# FPGA_DAC.net
KiCad netlist of a schematic drawn in Altium Designer
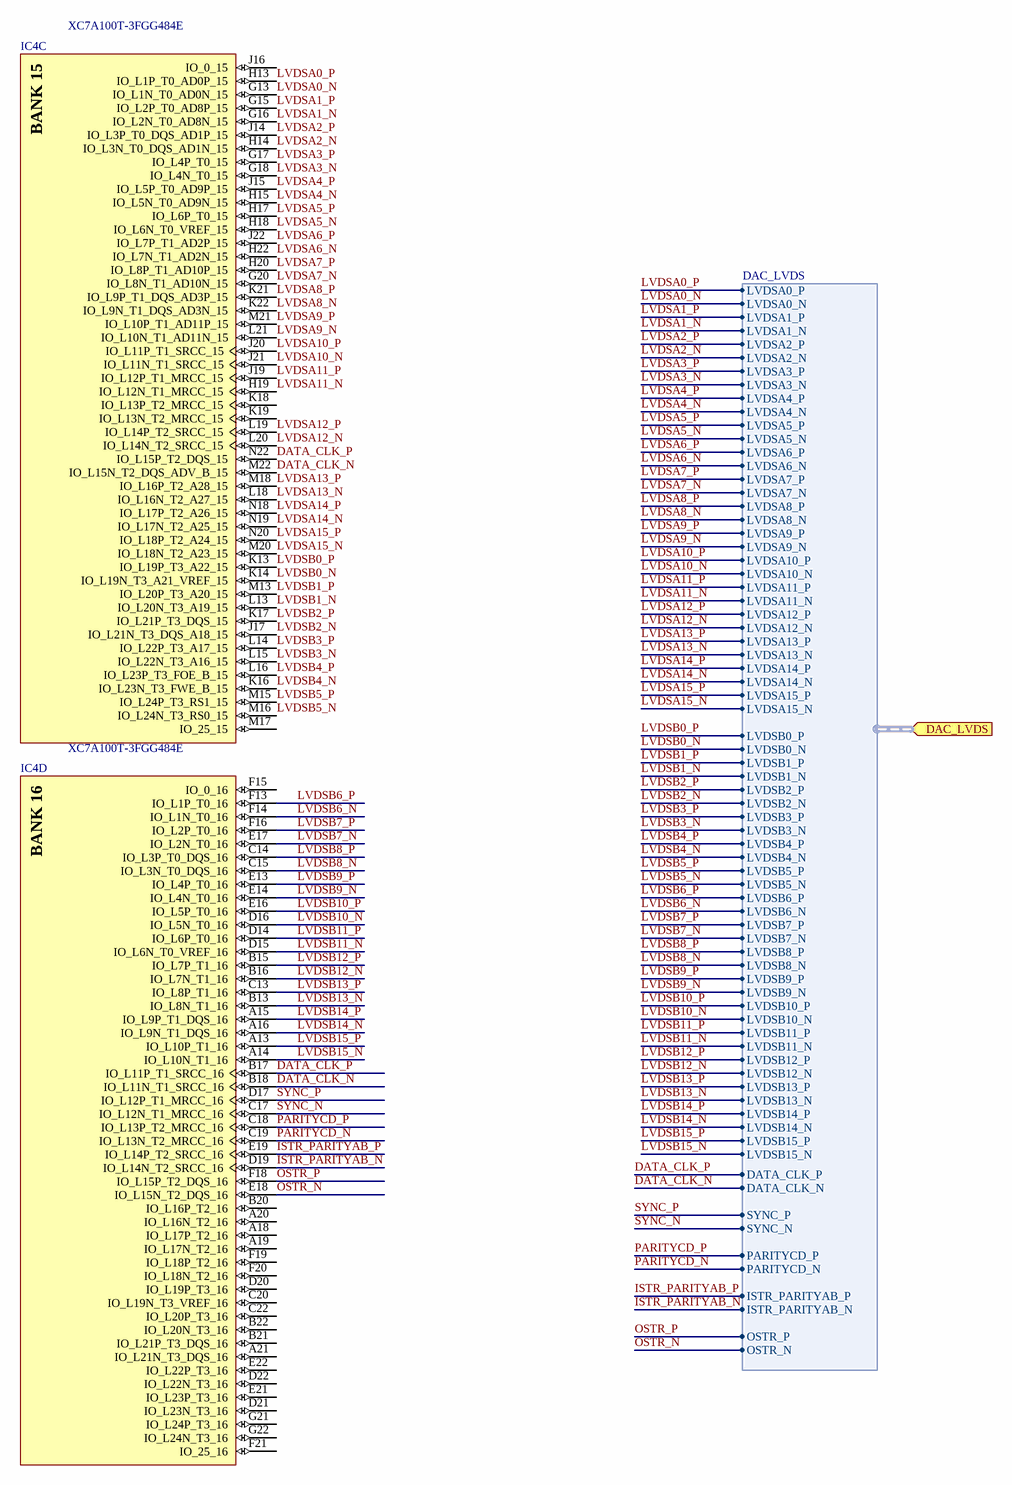
[diagram p0: FPGA_DAC.SchDoc]

(export (version "E")
  (design (tool "Eeschema 10.0.6"))
  (components
    (comp (ref "IC4")
      (value "XC7A100T-3FGG484E")
      (footprint "FGG484")
      (description "Artix-7 FPGA, 285 User I/Os, 4 GTP, 484-Ball BGA, Speed Grade 3, Extended Grade, Pb-Free")
      (fields (field (name "GENERIC PART NUMBER") "XC7A100T") (field (name "MANUFACTURER") "Xilinx"))
      (libsource (lib "Altium Content Vault") (part "XC7A100T-3FGG484E"))
    )
  )
  (nets
    (net (code "2") (name "/DATA_CLK_N") (class "Default")
      (node (ref "IC4") (pin "B18") (pinfunction "IO_L11N_T1_SRCC_16_B18") (pintype "bidirectional"))
      (node (ref "IC4") (pin "M22") (pinfunction "IO_L15N_T2_DQS_ADV_B_15_M22") (pintype "bidirectional"))
    )
    (net (code "3") (name "/DATA_CLK_P") (class "Default")
      (node (ref "IC4") (pin "B17") (pinfunction "IO_L11P_T1_SRCC_16_B17") (pintype "bidirectional"))
      (node (ref "IC4") (pin "N22") (pinfunction "IO_L15P_T2_DQS_15_N22") (pintype "bidirectional"))
    )
    (net (code "4") (name "/ISTR_PARITYAB_N") (class "Default")
      (node (ref "IC4") (pin "D19") (pinfunction "IO_L14N_T2_SRCC_16_D19") (pintype "bidirectional"))
    )
    (net (code "5") (name "/ISTR_PARITYAB_P") (class "Default")
      (node (ref "IC4") (pin "E19") (pinfunction "IO_L14P_T2_SRCC_16_E19") (pintype "bidirectional"))
    )
    (net (code "6") (name "/LVDSA0_N") (class "Default")
      (node (ref "IC4") (pin "G13") (pinfunction "IO_L1N_T0_AD0N_15_G13") (pintype "bidirectional"))
    )
    (net (code "7") (name "/LVDSA0_P") (class "Default")
      (node (ref "IC4") (pin "H13") (pinfunction "IO_L1P_T0_AD0P_15_H13") (pintype "bidirectional"))
    )
    (net (code "8") (name "/LVDSA1_N") (class "Default")
      (node (ref "IC4") (pin "G16") (pinfunction "IO_L2N_T0_AD8N_15_G16") (pintype "bidirectional"))
    )
    (net (code "9") (name "/LVDSA1_P") (class "Default")
      (node (ref "IC4") (pin "G15") (pinfunction "IO_L2P_T0_AD8P_15_G15") (pintype "bidirectional"))
    )
    (net (code "10") (name "/LVDSA2_N") (class "Default")
      (node (ref "IC4") (pin "H14") (pinfunction "IO_L3N_T0_DQS_AD1N_15_H14") (pintype "bidirectional"))
    )
    (net (code "11") (name "/LVDSA2_P") (class "Default")
      (node (ref "IC4") (pin "J14") (pinfunction "IO_L3P_T0_DQS_AD1P_15_J14") (pintype "bidirectional"))
    )
    (net (code "12") (name "/LVDSA3_N") (class "Default")
      (node (ref "IC4") (pin "G18") (pinfunction "IO_L4N_T0_15_G18") (pintype "bidirectional"))
    )
    (net (code "13") (name "/LVDSA3_P") (class "Default")
      (node (ref "IC4") (pin "G17") (pinfunction "IO_L4P_T0_15_G17") (pintype "bidirectional"))
    )
    (net (code "14") (name "/LVDSA4_N") (class "Default")
      (node (ref "IC4") (pin "H15") (pinfunction "IO_L5N_T0_AD9N_15_H15") (pintype "bidirectional"))
    )
    (net (code "15") (name "/LVDSA4_P") (class "Default")
      (node (ref "IC4") (pin "J15") (pinfunction "IO_L5P_T0_AD9P_15_J15") (pintype "bidirectional"))
    )
    (net (code "16") (name "/LVDSA5_N") (class "Default")
      (node (ref "IC4") (pin "H18") (pinfunction "IO_L6N_T0_VREF_15_H18") (pintype "bidirectional"))
    )
    (net (code "17") (name "/LVDSA5_P") (class "Default")
      (node (ref "IC4") (pin "H17") (pinfunction "IO_L6P_T0_15_H17") (pintype "bidirectional"))
    )
    (net (code "18") (name "/LVDSA6_N") (class "Default")
      (node (ref "IC4") (pin "H22") (pinfunction "IO_L7N_T1_AD2N_15_H22") (pintype "bidirectional"))
    )
    (net (code "19") (name "/LVDSA6_P") (class "Default")
      (node (ref "IC4") (pin "J22") (pinfunction "IO_L7P_T1_AD2P_15_J22") (pintype "bidirectional"))
    )
    (net (code "20") (name "/LVDSA7_N") (class "Default")
      (node (ref "IC4") (pin "G20") (pinfunction "IO_L8N_T1_AD10N_15_G20") (pintype "bidirectional"))
    )
    (net (code "21") (name "/LVDSA7_P") (class "Default")
      (node (ref "IC4") (pin "H20") (pinfunction "IO_L8P_T1_AD10P_15_H20") (pintype "bidirectional"))
    )
    (net (code "22") (name "/LVDSA8_N") (class "Default")
      (node (ref "IC4") (pin "K22") (pinfunction "IO_L9N_T1_DQS_AD3N_15_K22") (pintype "bidirectional"))
    )
    (net (code "23") (name "/LVDSA8_P") (class "Default")
      (node (ref "IC4") (pin "K21") (pinfunction "IO_L9P_T1_DQS_AD3P_15_K21") (pintype "bidirectional"))
    )
    (net (code "24") (name "/LVDSA9_N") (class "Default")
      (node (ref "IC4") (pin "L21") (pinfunction "IO_L10N_T1_AD11N_15_L21") (pintype "bidirectional"))
    )
    (net (code "25") (name "/LVDSA9_P") (class "Default")
      (node (ref "IC4") (pin "M21") (pinfunction "IO_L10P_T1_AD11P_15_M21") (pintype "bidirectional"))
    )
    (net (code "26") (name "/LVDSA10_N") (class "Default")
      (node (ref "IC4") (pin "J21") (pinfunction "IO_L11N_T1_SRCC_15_J21") (pintype "bidirectional"))
    )
    (net (code "27") (name "/LVDSA10_P") (class "Default")
      (node (ref "IC4") (pin "J20") (pinfunction "IO_L11P_T1_SRCC_15_J20") (pintype "bidirectional"))
    )
    (net (code "28") (name "/LVDSA11_N") (class "Default")
      (node (ref "IC4") (pin "H19") (pinfunction "IO_L12N_T1_MRCC_15_H19") (pintype "bidirectional"))
    )
    (net (code "29") (name "/LVDSA11_P") (class "Default")
      (node (ref "IC4") (pin "J19") (pinfunction "IO_L12P_T1_MRCC_15_J19") (pintype "bidirectional"))
    )
    (net (code "30") (name "/LVDSA12_N") (class "Default")
      (node (ref "IC4") (pin "L20") (pinfunction "IO_L14N_T2_SRCC_15_L20") (pintype "bidirectional"))
    )
    (net (code "31") (name "/LVDSA12_P") (class "Default")
      (node (ref "IC4") (pin "L19") (pinfunction "IO_L14P_T2_SRCC_15_L19") (pintype "bidirectional"))
    )
    (net (code "32") (name "/LVDSA13_N") (class "Default")
      (node (ref "IC4") (pin "L18") (pinfunction "IO_L16N_T2_A27_15_L18") (pintype "bidirectional"))
    )
    (net (code "33") (name "/LVDSA13_P") (class "Default")
      (node (ref "IC4") (pin "M18") (pinfunction "IO_L16P_T2_A28_15_M18") (pintype "bidirectional"))
    )
    (net (code "34") (name "/LVDSA14_N") (class "Default")
      (node (ref "IC4") (pin "N19") (pinfunction "IO_L17N_T2_A25_15_N19") (pintype "bidirectional"))
    )
    (net (code "35") (name "/LVDSA14_P") (class "Default")
      (node (ref "IC4") (pin "N18") (pinfunction "IO_L17P_T2_A26_15_N18") (pintype "bidirectional"))
    )
    (net (code "36") (name "/LVDSA15_N") (class "Default")
      (node (ref "IC4") (pin "M20") (pinfunction "IO_L18N_T2_A23_15_M20") (pintype "bidirectional"))
    )
    (net (code "37") (name "/LVDSA15_P") (class "Default")
      (node (ref "IC4") (pin "N20") (pinfunction "IO_L18P_T2_A24_15_N20") (pintype "bidirectional"))
    )
    (net (code "38") (name "/LVDSB0_N") (class "Default")
      (node (ref "IC4") (pin "K14") (pinfunction "IO_L19N_T3_A21_VREF_15_K14") (pintype "bidirectional"))
    )
    (net (code "39") (name "/LVDSB0_P") (class "Default")
      (node (ref "IC4") (pin "K13") (pinfunction "IO_L19P_T3_A22_15_K13") (pintype "bidirectional"))
    )
    (net (code "40") (name "/LVDSB1_N") (class "Default")
      (node (ref "IC4") (pin "L13") (pinfunction "IO_L20N_T3_A19_15_L13") (pintype "bidirectional"))
    )
    (net (code "41") (name "/LVDSB1_P") (class "Default")
      (node (ref "IC4") (pin "M13") (pinfunction "IO_L20P_T3_A20_15_M13") (pintype "bidirectional"))
    )
    (net (code "42") (name "/LVDSB2_N") (class "Default")
      (node (ref "IC4") (pin "J17") (pinfunction "IO_L21N_T3_DQS_A18_15_J17") (pintype "bidirectional"))
    )
    (net (code "43") (name "/LVDSB2_P") (class "Default")
      (node (ref "IC4") (pin "K17") (pinfunction "IO_L21P_T3_DQS_15_K17") (pintype "bidirectional"))
    )
    (net (code "44") (name "/LVDSB3_N") (class "Default")
      (node (ref "IC4") (pin "L15") (pinfunction "IO_L22N_T3_A16_15_L15") (pintype "bidirectional"))
    )
    (net (code "45") (name "/LVDSB3_P") (class "Default")
      (node (ref "IC4") (pin "L14") (pinfunction "IO_L22P_T3_A17_15_L14") (pintype "bidirectional"))
    )
    (net (code "46") (name "/LVDSB4_N") (class "Default")
      (node (ref "IC4") (pin "K16") (pinfunction "IO_L23N_T3_FWE_B_15_K16") (pintype "bidirectional"))
    )
    (net (code "47") (name "/LVDSB4_P") (class "Default")
      (node (ref "IC4") (pin "L16") (pinfunction "IO_L23P_T3_FOE_B_15_L16") (pintype "bidirectional"))
    )
    (net (code "48") (name "/LVDSB5_N") (class "Default")
      (node (ref "IC4") (pin "M16") (pinfunction "IO_L24N_T3_RS0_15_M16") (pintype "bidirectional"))
    )
    (net (code "49") (name "/LVDSB5_P") (class "Default")
      (node (ref "IC4") (pin "M15") (pinfunction "IO_L24P_T3_RS1_15_M15") (pintype "bidirectional"))
    )
    (net (code "50") (name "/LVDSB6_N") (class "Default")
      (node (ref "IC4") (pin "F14") (pinfunction "IO_L1N_T0_16_F14") (pintype "bidirectional"))
    )
    (net (code "51") (name "/LVDSB6_P") (class "Default")
      (node (ref "IC4") (pin "F13") (pinfunction "IO_L1P_T0_16_F13") (pintype "bidirectional"))
    )
    (net (code "52") (name "/LVDSB7_N") (class "Default")
      (node (ref "IC4") (pin "E17") (pinfunction "IO_L2N_T0_16_E17") (pintype "bidirectional"))
    )
    (net (code "53") (name "/LVDSB7_P") (class "Default")
      (node (ref "IC4") (pin "F16") (pinfunction "IO_L2P_T0_16_F16") (pintype "bidirectional"))
    )
    (net (code "54") (name "/LVDSB8_N") (class "Default")
      (node (ref "IC4") (pin "C15") (pinfunction "IO_L3N_T0_DQS_16_C15") (pintype "bidirectional"))
    )
    (net (code "55") (name "/LVDSB8_P") (class "Default")
      (node (ref "IC4") (pin "C14") (pinfunction "IO_L3P_T0_DQS_16_C14") (pintype "bidirectional"))
    )
    (net (code "56") (name "/LVDSB9_N") (class "Default")
      (node (ref "IC4") (pin "E14") (pinfunction "IO_L4N_T0_16_E14") (pintype "bidirectional"))
    )
    (net (code "57") (name "/LVDSB9_P") (class "Default")
      (node (ref "IC4") (pin "E13") (pinfunction "IO_L4P_T0_16_E13") (pintype "bidirectional"))
    )
    (net (code "58") (name "/LVDSB10_N") (class "Default")
      (node (ref "IC4") (pin "D16") (pinfunction "IO_L5N_T0_16_D16") (pintype "bidirectional"))
    )
    (net (code "59") (name "/LVDSB10_P") (class "Default")
      (node (ref "IC4") (pin "E16") (pinfunction "IO_L5P_T0_16_E16") (pintype "bidirectional"))
    )
    (net (code "60") (name "/LVDSB11_N") (class "Default")
      (node (ref "IC4") (pin "D15") (pinfunction "IO_L6N_T0_VREF_16_D15") (pintype "bidirectional"))
    )
    (net (code "61") (name "/LVDSB11_P") (class "Default")
      (node (ref "IC4") (pin "D14") (pinfunction "IO_L6P_T0_16_D14") (pintype "bidirectional"))
    )
    (net (code "62") (name "/LVDSB12_N") (class "Default")
      (node (ref "IC4") (pin "B16") (pinfunction "IO_L7N_T1_16_B16") (pintype "bidirectional"))
    )
    (net (code "63") (name "/LVDSB12_P") (class "Default")
      (node (ref "IC4") (pin "B15") (pinfunction "IO_L7P_T1_16_B15") (pintype "bidirectional"))
    )
    (net (code "64") (name "/LVDSB13_N") (class "Default")
      (node (ref "IC4") (pin "B13") (pinfunction "IO_L8N_T1_16_B13") (pintype "bidirectional"))
    )
    (net (code "65") (name "/LVDSB13_P") (class "Default")
      (node (ref "IC4") (pin "C13") (pinfunction "IO_L8P_T1_16_C13") (pintype "bidirectional"))
    )
    (net (code "66") (name "/LVDSB14_N") (class "Default")
      (node (ref "IC4") (pin "A16") (pinfunction "IO_L9N_T1_DQS_16_A16") (pintype "bidirectional"))
    )
    (net (code "67") (name "/LVDSB14_P") (class "Default")
      (node (ref "IC4") (pin "A15") (pinfunction "IO_L9P_T1_DQS_16_A15") (pintype "bidirectional"))
    )
    (net (code "68") (name "/LVDSB15_N") (class "Default")
      (node (ref "IC4") (pin "A14") (pinfunction "IO_L10N_T1_16_A14") (pintype "bidirectional"))
    )
    (net (code "69") (name "/LVDSB15_P") (class "Default")
      (node (ref "IC4") (pin "A13") (pinfunction "IO_L10P_T1_16_A13") (pintype "bidirectional"))
    )
    (net (code "70") (name "/OSTR_N") (class "Default")
      (node (ref "IC4") (pin "E18") (pinfunction "IO_L15N_T2_DQS_16_E18") (pintype "bidirectional"))
    )
    (net (code "71") (name "/OSTR_P") (class "Default")
      (node (ref "IC4") (pin "F18") (pinfunction "IO_L15P_T2_DQS_16_F18") (pintype "bidirectional"))
    )
    (net (code "72") (name "/PARITYCD_N") (class "Default")
      (node (ref "IC4") (pin "C19") (pinfunction "IO_L13N_T2_MRCC_16_C19") (pintype "bidirectional"))
    )
    (net (code "73") (name "/PARITYCD_P") (class "Default")
      (node (ref "IC4") (pin "C18") (pinfunction "IO_L13P_T2_MRCC_16_C18") (pintype "bidirectional"))
    )
    (net (code "74") (name "/SYNC_N") (class "Default")
      (node (ref "IC4") (pin "C17") (pinfunction "IO_L12N_T1_MRCC_16_C17") (pintype "bidirectional"))
    )
    (net (code "75") (name "/SYNC_P") (class "Default")
      (node (ref "IC4") (pin "D17") (pinfunction "IO_L12P_T1_MRCC_16_D17") (pintype "bidirectional"))
    )
    (net (code "77") (name "unconnected-(IC4C-IO_0_15-PadJ16)") (class "Default")
      (node (ref "IC4") (pin "J16") (pinfunction "IO_0_15_J16") (pintype "bidirectional"))
    )
    (net (code "78") (name "unconnected-(IC4C-IO_25_15-PadM17)") (class "Default")
      (node (ref "IC4") (pin "M17") (pinfunction "IO_25_15_M17") (pintype "bidirectional"))
    )
    (net (code "79") (name "unconnected-(IC4C-IO_L13N_T2_MRCC_15-PadK19)") (class "Default")
      (node (ref "IC4") (pin "K19") (pinfunction "IO_L13N_T2_MRCC_15_K19") (pintype "bidirectional"))
    )
    (net (code "80") (name "unconnected-(IC4C-IO_L13P_T2_MRCC_15-PadK18)") (class "Default")
      (node (ref "IC4") (pin "K18") (pinfunction "IO_L13P_T2_MRCC_15_K18") (pintype "bidirectional"))
    )
    (net (code "81") (name "unconnected-(IC4D-IO_0_16-PadF15)") (class "Default")
      (node (ref "IC4") (pin "F15") (pinfunction "IO_0_16_F15") (pintype "bidirectional"))
    )
    (net (code "82") (name "unconnected-(IC4D-IO_25_16-PadF21)") (class "Default")
      (node (ref "IC4") (pin "F21") (pinfunction "IO_25_16_F21") (pintype "bidirectional"))
    )
    (net (code "83") (name "unconnected-(IC4D-IO_L16N_T2_16-PadA20)") (class "Default")
      (node (ref "IC4") (pin "A20") (pinfunction "IO_L16N_T2_16_A20") (pintype "bidirectional"))
    )
    (net (code "84") (name "unconnected-(IC4D-IO_L16P_T2_16-PadB20)") (class "Default")
      (node (ref "IC4") (pin "B20") (pinfunction "IO_L16P_T2_16_B20") (pintype "bidirectional"))
    )
    (net (code "85") (name "unconnected-(IC4D-IO_L17N_T2_16-PadA19)") (class "Default")
      (node (ref "IC4") (pin "A19") (pinfunction "IO_L17N_T2_16_A19") (pintype "bidirectional"))
    )
    (net (code "86") (name "unconnected-(IC4D-IO_L17P_T2_16-PadA18)") (class "Default")
      (node (ref "IC4") (pin "A18") (pinfunction "IO_L17P_T2_16_A18") (pintype "bidirectional"))
    )
    (net (code "87") (name "unconnected-(IC4D-IO_L18N_T2_16-PadF20)") (class "Default")
      (node (ref "IC4") (pin "F20") (pinfunction "IO_L18N_T2_16_F20") (pintype "bidirectional"))
    )
    (net (code "88") (name "unconnected-(IC4D-IO_L18P_T2_16-PadF19)") (class "Default")
      (node (ref "IC4") (pin "F19") (pinfunction "IO_L18P_T2_16_F19") (pintype "bidirectional"))
    )
    (net (code "89") (name "unconnected-(IC4D-IO_L19N_T3_VREF_16-PadC20)") (class "Default")
      (node (ref "IC4") (pin "C20") (pinfunction "IO_L19N_T3_VREF_16_C20") (pintype "bidirectional"))
    )
    (net (code "90") (name "unconnected-(IC4D-IO_L19P_T3_16-PadD20)") (class "Default")
      (node (ref "IC4") (pin "D20") (pinfunction "IO_L19P_T3_16_D20") (pintype "bidirectional"))
    )
    (net (code "91") (name "unconnected-(IC4D-IO_L20N_T3_16-PadB22)") (class "Default")
      (node (ref "IC4") (pin "B22") (pinfunction "IO_L20N_T3_16_B22") (pintype "bidirectional"))
    )
    (net (code "92") (name "unconnected-(IC4D-IO_L20P_T3_16-PadC22)") (class "Default")
      (node (ref "IC4") (pin "C22") (pinfunction "IO_L20P_T3_16_C22") (pintype "bidirectional"))
    )
    (net (code "93") (name "unconnected-(IC4D-IO_L21N_T3_DQS_16-PadA21)") (class "Default")
      (node (ref "IC4") (pin "A21") (pinfunction "IO_L21N_T3_DQS_16_A21") (pintype "bidirectional"))
    )
    (net (code "94") (name "unconnected-(IC4D-IO_L21P_T3_DQS_16-PadB21)") (class "Default")
      (node (ref "IC4") (pin "B21") (pinfunction "IO_L21P_T3_DQS_16_B21") (pintype "bidirectional"))
    )
    (net (code "95") (name "unconnected-(IC4D-IO_L22N_T3_16-PadD22)") (class "Default")
      (node (ref "IC4") (pin "D22") (pinfunction "IO_L22N_T3_16_D22") (pintype "bidirectional"))
    )
    (net (code "96") (name "unconnected-(IC4D-IO_L22P_T3_16-PadE22)") (class "Default")
      (node (ref "IC4") (pin "E22") (pinfunction "IO_L22P_T3_16_E22") (pintype "bidirectional"))
    )
    (net (code "97") (name "unconnected-(IC4D-IO_L23N_T3_16-PadD21)") (class "Default")
      (node (ref "IC4") (pin "D21") (pinfunction "IO_L23N_T3_16_D21") (pintype "bidirectional"))
    )
    (net (code "98") (name "unconnected-(IC4D-IO_L23P_T3_16-PadE21)") (class "Default")
      (node (ref "IC4") (pin "E21") (pinfunction "IO_L23P_T3_16_E21") (pintype "bidirectional"))
    )
    (net (code "99") (name "unconnected-(IC4D-IO_L24N_T3_16-PadG22)") (class "Default")
      (node (ref "IC4") (pin "G22") (pinfunction "IO_L24N_T3_16_G22") (pintype "bidirectional"))
    )
    (net (code "100") (name "unconnected-(IC4D-IO_L24P_T3_16-PadG21)") (class "Default")
      (node (ref "IC4") (pin "G21") (pinfunction "IO_L24P_T3_16_G21") (pintype "bidirectional"))
    )
  )
)
